# Adafruit_Feather_M0_Adalogger.net
KiCad netlist of a schematic drawn in EAGLE
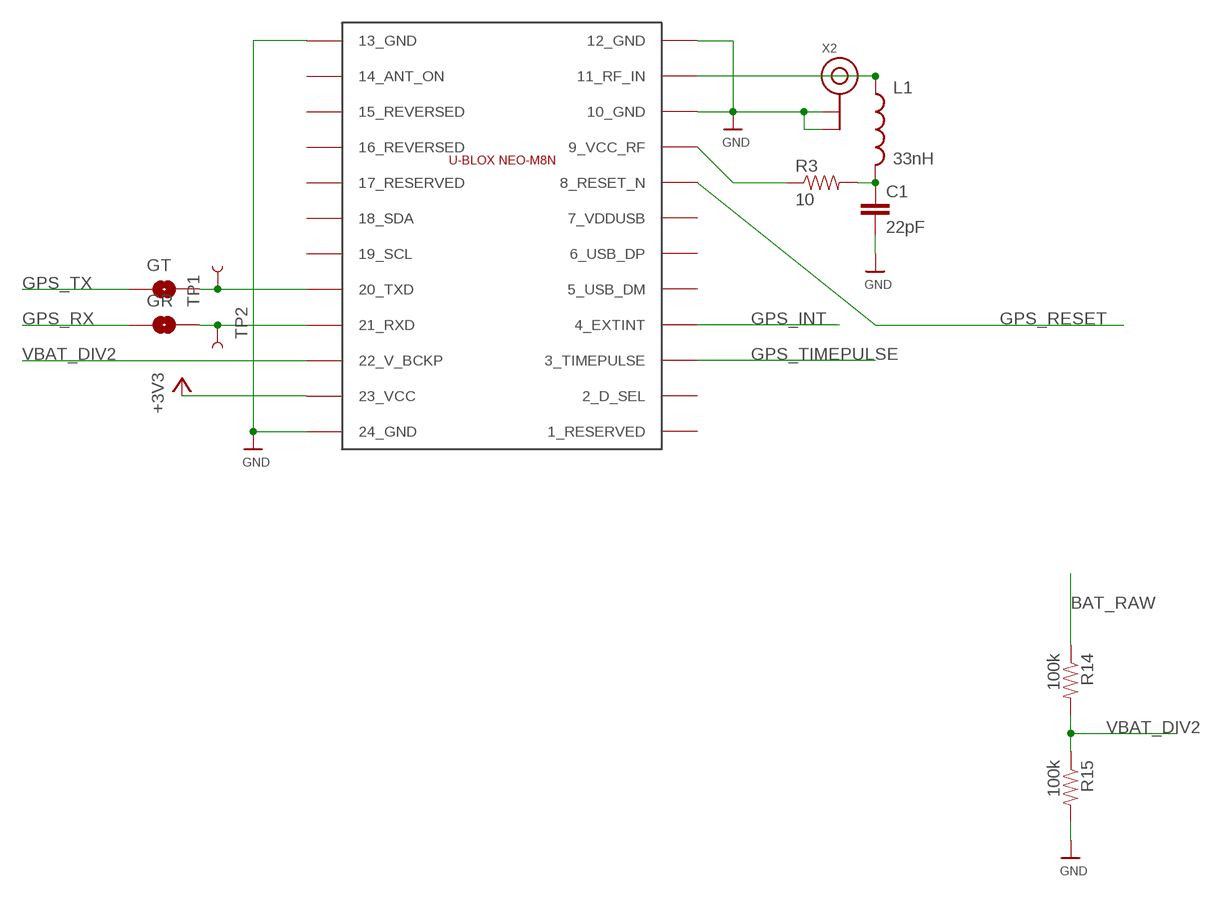
[diagram p0: schematic, sheet 1, part 1 of 2]
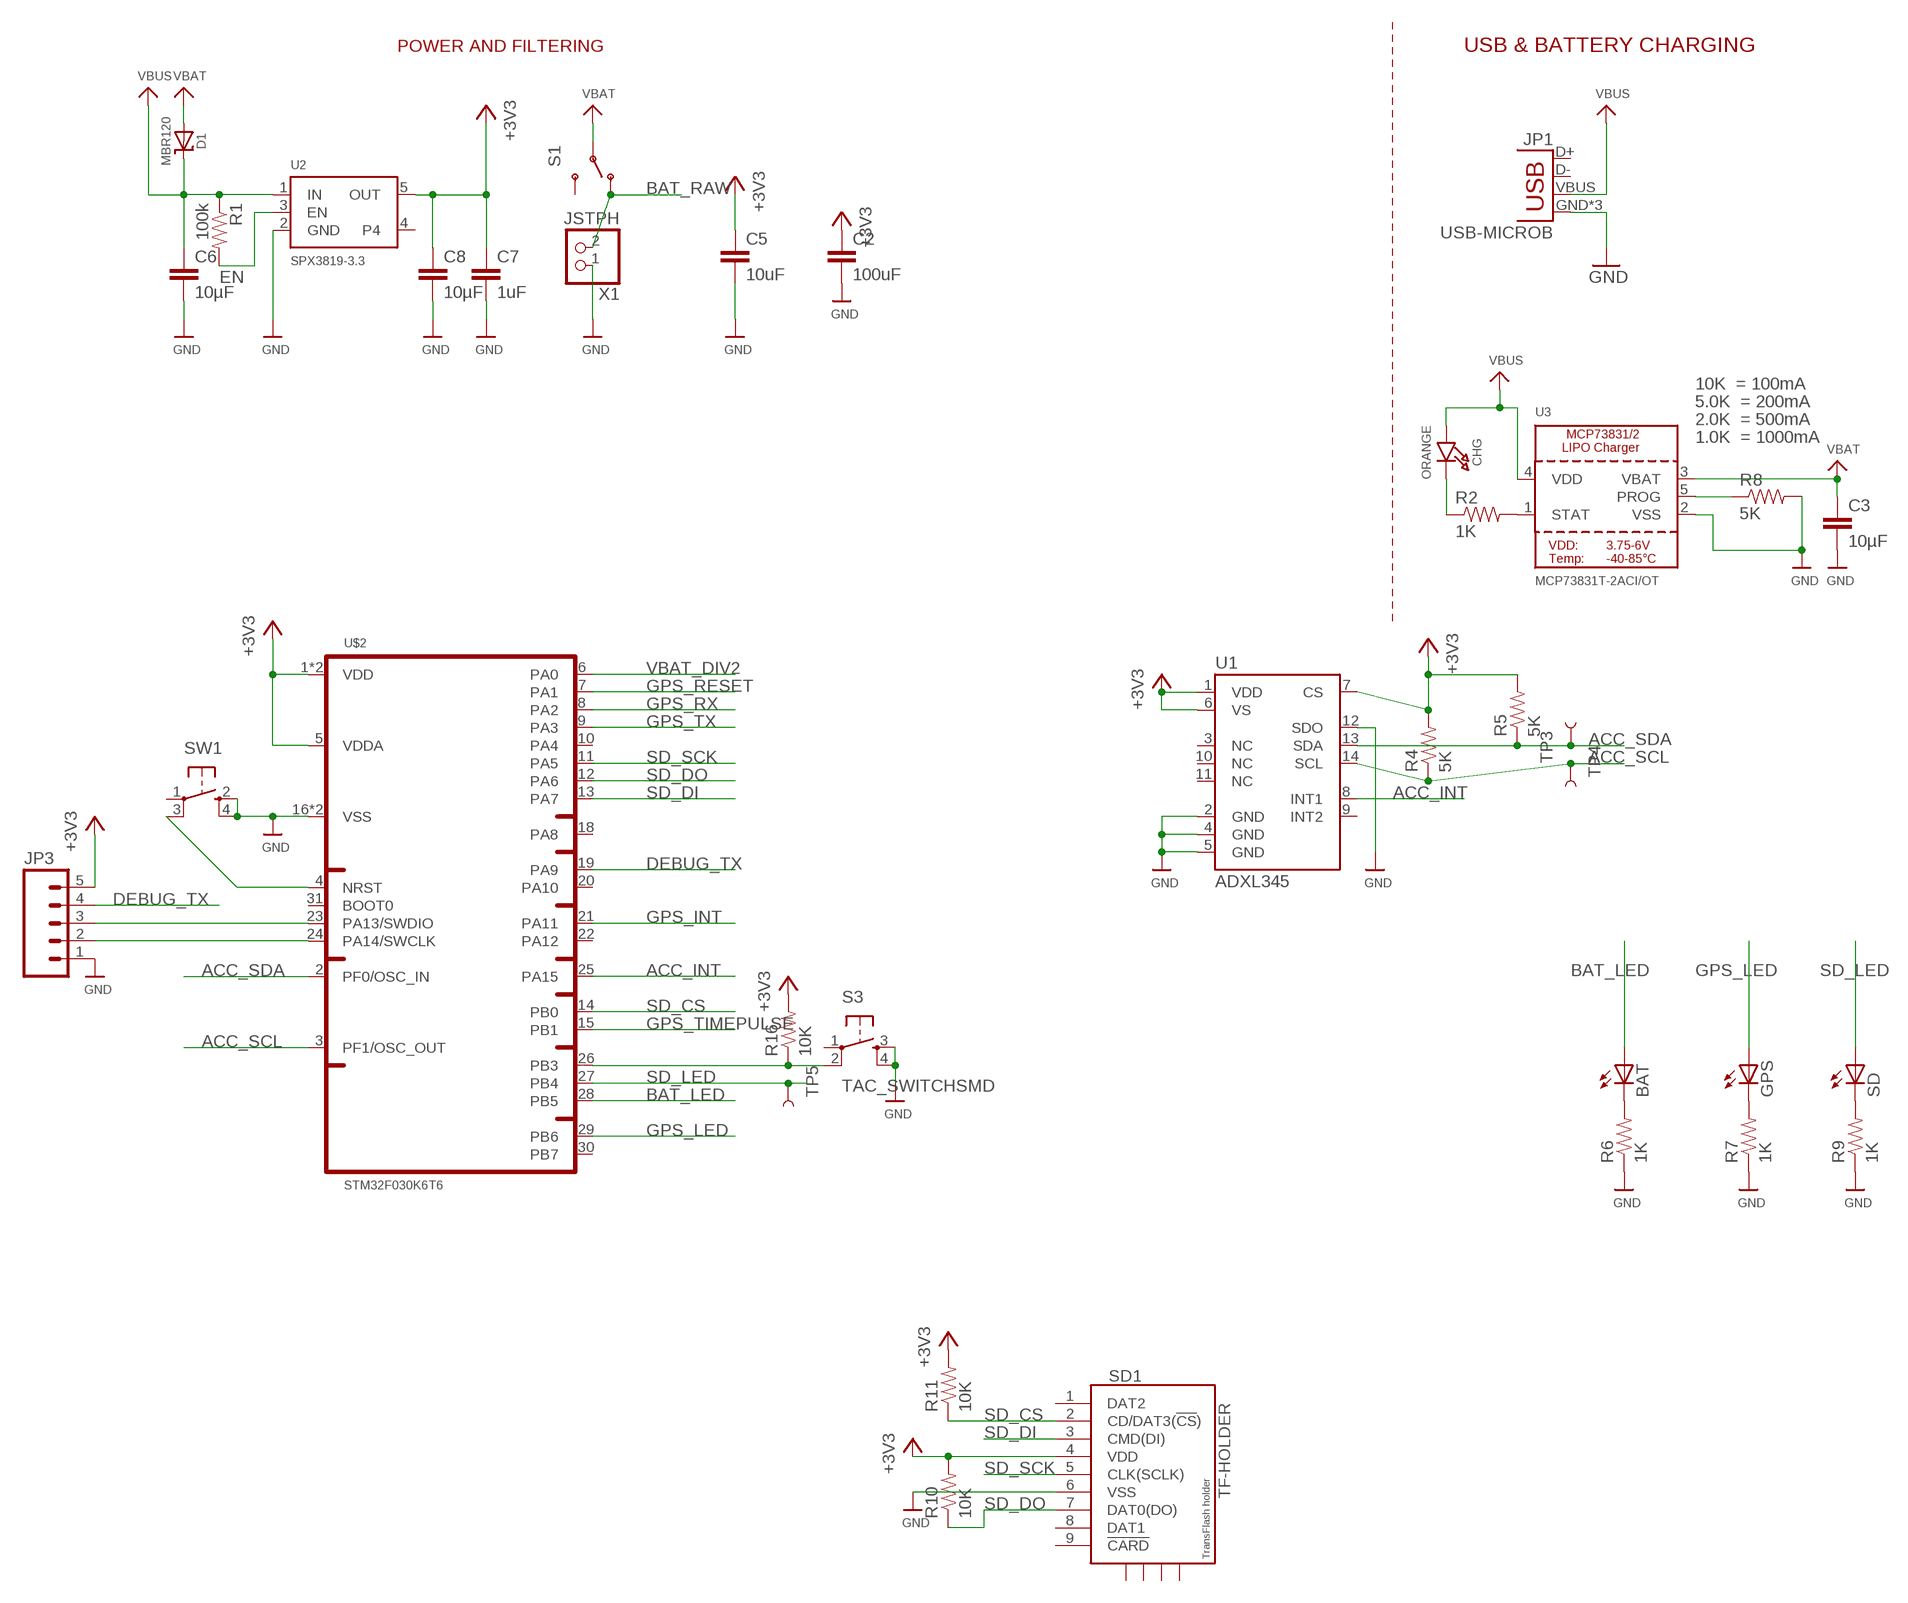
[diagram p1: schematic, sheet 1, part 2 of 2]

(export (version "E")
  (design (tool "Eeschema 10.0.6"))
  (components
    (comp (ref "BAT")
      (value "LEDCHIPLED_0805")
      (footprint "eagle-import:CHIPLED_0805")
      (libsource (lib "eagle-import") (part "LEDCHIPLED_0805"))
    )
    (comp (ref "C1")
      (value "22pF")
      (footprint "eagle-import:0805")
      (libsource (lib "eagle-import") (part "CAP0805"))
    )
    (comp (ref "C2")
      (value "100uF")
      (footprint "eagle-import:1210")
      (libsource (lib "eagle-import") (part "100UF6.3V20%(1210)"))
    )
    (comp (ref "C3")
      (value "10µF")
      (footprint "eagle-import:0805")
      (libsource (lib "eagle-import") (part "CAP0805"))
    )
    (comp (ref "C5")
      (value "10uF")
      (footprint "eagle-import:0805")
      (libsource (lib "eagle-import") (part "CAP0805"))
    )
    (comp (ref "C6")
      (value "10µF")
      (footprint "eagle-import:0805")
      (libsource (lib "eagle-import") (part "CAP0805"))
    )
    (comp (ref "C7")
      (value "1uF")
      (footprint "eagle-import:0805")
      (libsource (lib "eagle-import") (part "CAP0805"))
    )
    (comp (ref "C8")
      (value "10µF")
      (footprint "eagle-import:0805")
      (libsource (lib "eagle-import") (part "CAP0805"))
    )
    (comp (ref "CHG")
      (value "ORANGE")
      (footprint "eagle-import:CHIPLED_0805_NOOUTLINE")
      (libsource (lib "eagle-import") (part "LED0805_NOOUTLINE"))
    )
    (comp (ref "D1")
      (value "MBR120")
      (footprint "eagle-import:SOD-123")
      (libsource (lib "eagle-import") (part "DIODE-SCHOTTKYSOD-123"))
    )
    (comp (ref "DEKU1")
      (value "UBLOX_NEO-M8N")
      (footprint "eagle-import:UBLOX_NEO-M8N")
      (libsource (lib "eagle-import") (part "UBLOX_NEO-M8N"))
    )
    (comp (ref "GPS")
      (value "LEDCHIPLED_0805")
      (footprint "eagle-import:CHIPLED_0805")
      (libsource (lib "eagle-import") (part "LEDCHIPLED_0805"))
    )
    (comp (ref "GR")
      (value "JUMPER-PAD-2-NO")
      (footprint "eagle-import:PAD-JUMPER-2-NO_NO_SILK")
      (libsource (lib "eagle-import") (part "JUMPER-PAD-2-NO"))
    )
    (comp (ref "GT")
      (value "JUMPER-PAD-2-NO")
      (footprint "eagle-import:PAD-JUMPER-2-NO_NO_SILK")
      (libsource (lib "eagle-import") (part "JUMPER-PAD-2-NO"))
    )
    (comp (ref "JP1")
      (value "USB-MICROB")
      (footprint "eagle-import:USB-MICROB")
      (libsource (lib "eagle-import") (part "USB-MICROB"))
    )
    (comp (ref "JP3")
      (value "M05NO_SILK")
      (footprint "eagle-import:1X05_NO_SILK")
      (libsource (lib "eagle-import") (part "M05NO_SILK"))
    )
    (comp (ref "L1")
      (value "33nH")
      (footprint "eagle-import:0805")
      (libsource (lib "eagle-import") (part "INDUCTOR0805"))
    )
    (comp (ref "R1")
      (value "100k")
      (footprint "eagle-import:0805")
      (libsource (lib "eagle-import") (part "RESISTOR0805-RES"))
    )
    (comp (ref "R2")
      (value "1K")
      (footprint "eagle-import:0805")
      (libsource (lib "eagle-import") (part "RESISTOR0805-RES"))
    )
    (comp (ref "R3")
      (value "10")
      (footprint "eagle-import:0805")
      (libsource (lib "eagle-import") (part "RESISTOR0805-RES"))
    )
    (comp (ref "R4")
      (value "5K")
      (footprint "eagle-import:0805")
      (libsource (lib "eagle-import") (part "RESISTOR0805-RES"))
    )
    (comp (ref "R5")
      (value "5K")
      (footprint "eagle-import:0805")
      (libsource (lib "eagle-import") (part "RESISTOR0805-RES"))
    )
    (comp (ref "R6")
      (value "1K")
      (footprint "eagle-import:0805")
      (libsource (lib "eagle-import") (part "RESISTOR0805-RES"))
    )
    (comp (ref "R7")
      (value "1K")
      (footprint "eagle-import:0805")
      (libsource (lib "eagle-import") (part "RESISTOR0805-RES"))
    )
    (comp (ref "R8")
      (value "5K")
      (footprint "eagle-import:0805")
      (libsource (lib "eagle-import") (part "RESISTOR0805-RES"))
    )
    (comp (ref "R9")
      (value "1K")
      (footprint "eagle-import:0805")
      (libsource (lib "eagle-import") (part "RESISTOR0805-RES"))
    )
    (comp (ref "R10")
      (value "10K")
      (footprint "eagle-import:0805")
      (libsource (lib "eagle-import") (part "RESISTOR0805-RES"))
    )
    (comp (ref "R11")
      (value "10K")
      (footprint "eagle-import:0805")
      (libsource (lib "eagle-import") (part "RESISTOR0805-RES"))
    )
    (comp (ref "R14")
      (value "100k")
      (footprint "eagle-import:0805")
      (libsource (lib "eagle-import") (part "RESISTOR0805-RES"))
    )
    (comp (ref "R15")
      (value "100k")
      (footprint "eagle-import:0805")
      (libsource (lib "eagle-import") (part "RESISTOR0805-RES"))
    )
    (comp (ref "R16")
      (value "10K")
      (footprint "eagle-import:0805")
      (libsource (lib "eagle-import") (part "RESISTOR0805-RES"))
    )
    (comp (ref "S1")
      (value "SWITCH-SPDT-SMD-A")
      (footprint "eagle-import:SWITCH-SPST-SMD-A")
      (libsource (lib "eagle-import") (part "SWITCH-SPDT-SMD-A"))
    )
    (comp (ref "S3")
      (value "TAC_SWITCHSMD")
      (footprint "eagle-import:TACTILE-SWITCH-SMD")
      (libsource (lib "eagle-import") (part "TAC_SWITCHSMD"))
    )
    (comp (ref "SD")
      (value "LEDCHIPLED_0805")
      (footprint "eagle-import:CHIPLED_0805")
      (libsource (lib "eagle-import") (part "LEDCHIPLED_0805"))
    )
    (comp (ref "SD1")
      (value "TF-HOLDER")
      (footprint "eagle-import:TF-PULL")
      (libsource (lib "eagle-import") (part "TF-HOLDER"))
    )
    (comp (ref "SW1")
      (value "SPST_TACT-KMR2")
      (footprint "eagle-import:KMR2")
      (libsource (lib "eagle-import") (part "SPST_TACT-KMR2"))
    )
    (comp (ref "TP1")
      (value "TEST-POINT3X5")
      (footprint "eagle-import:PAD.03X.05")
      (libsource (lib "eagle-import") (part "TEST-POINT3X5"))
    )
    (comp (ref "TP2")
      (value "TEST-POINT3X5")
      (footprint "eagle-import:PAD.03X.05")
      (libsource (lib "eagle-import") (part "TEST-POINT3X5"))
    )
    (comp (ref "TP3")
      (value "TEST-POINT3")
      (footprint "eagle-import:PAD.03X.03")
      (libsource (lib "eagle-import") (part "TEST-POINT3"))
    )
    (comp (ref "TP4")
      (value "TEST-POINT3X5")
      (footprint "eagle-import:PAD.03X.05")
      (libsource (lib "eagle-import") (part "TEST-POINT3X5"))
    )
    (comp (ref "TP5")
      (value "TEST-POINT3X5")
      (footprint "eagle-import:PAD.03X.05")
      (libsource (lib "eagle-import") (part "TEST-POINT3X5"))
    )
    (comp (ref "U$2")
      (value "STM32F030K6T6")
      (footprint "eagle-import:TQFP32-08")
      (libsource (lib "eagle-import") (part "STM32F030K6T6"))
    )
    (comp (ref "U1")
      (value "ADXL345")
      (footprint "eagle-import:LGA14")
      (libsource (lib "eagle-import") (part "ADXL345"))
    )
    (comp (ref "U2")
      (value "SPX3819-3.3")
      (footprint "eagle-import:SOT23-5")
      (libsource (lib "eagle-import") (part "VREG_SOT23-5"))
    )
    (comp (ref "U3")
      (value "MCP73831T-2ACI/OT")
      (footprint "eagle-import:SOT23-5")
      (libsource (lib "eagle-import") (part "MCP73831/2"))
    )
    (comp (ref "X1")
      (value "JSTPH")
      (footprint "eagle-import:JSTPH2")
      (libsource (lib "eagle-import") (part "CON_JST_PH_2PIN"))
    )
    (comp (ref "X2")
      (value "ANTENNA_U.FL")
      (footprint "eagle-import:U.FL")
      (libsource (lib "eagle-import") (part "ANTENNA_U.FL"))
    )
  )
  (nets
    (net (code "1") (name "+3V3") (class "Default")
      (node (ref "C2") (pin "1") (pinfunction "1_1") (pintype "passive"))
      (node (ref "C5") (pin "1") (pinfunction "1_1") (pintype "passive"))
      (node (ref "C7") (pin "1") (pinfunction "1_1") (pintype "passive"))
      (node (ref "C8") (pin "1") (pinfunction "1_1") (pintype "passive"))
      (node (ref "DEKU1") (pin "23_VCC") (pinfunction "23_VCC_23_VCC") (pintype "bidirectional"))
      (node (ref "JP3") (pin "5") (pinfunction "5_5") (pintype "passive"))
      (node (ref "R10") (pin "2") (pinfunction "2_2") (pintype "passive"))
      (node (ref "R11") (pin "2") (pinfunction "2_2") (pintype "passive"))
      (node (ref "R16") (pin "2") (pinfunction "2_2") (pintype "passive"))
      (node (ref "R4") (pin "2") (pinfunction "2_2") (pintype "passive"))
      (node (ref "R5") (pin "2") (pinfunction "2_2") (pintype "passive"))
      (node (ref "SD1") (pin "4") (pinfunction "VDD_4") (pintype "power_in"))
      (node (ref "U$2") (pin "1") (pinfunction "VDD_1") (pintype "bidirectional"))
      (node (ref "U$2") (pin "17") (pinfunction "VDD_17") (pintype "bidirectional"))
      (node (ref "U$2") (pin "5") (pinfunction "VDDA_5") (pintype "bidirectional"))
      (node (ref "U1") (pin "1") (pinfunction "VDD_1") (pintype "bidirectional"))
      (node (ref "U1") (pin "6") (pinfunction "VS_6") (pintype "bidirectional"))
      (node (ref "U1") (pin "7") (pinfunction "CS_7") (pintype "bidirectional"))
      (node (ref "U2") (pin "5") (pinfunction "OUT_5") (pintype "power_in"))
    )
    (net (code "2") (name "/ACC_INT") (class "Default")
      (node (ref "U$2") (pin "25") (pinfunction "PA15_25") (pintype "bidirectional"))
      (node (ref "U1") (pin "8") (pinfunction "INT1_8") (pintype "bidirectional"))
    )
    (net (code "3") (name "/ACC_SCL") (class "Default")
      (node (ref "R4") (pin "1") (pinfunction "1_1") (pintype "passive"))
      (node (ref "TP4") (pin "P$1") (pinfunction "1_P$1") (pintype "bidirectional"))
      (node (ref "U$2") (pin "3") (pinfunction "PF1/OSC_OUT_3") (pintype "bidirectional"))
      (node (ref "U1") (pin "14") (pinfunction "SCL_14") (pintype "bidirectional"))
    )
    (net (code "4") (name "/ACC_SDA") (class "Default")
      (node (ref "R5") (pin "1") (pinfunction "1_1") (pintype "passive"))
      (node (ref "TP3") (pin "P$1") (pinfunction "1_P$1") (pintype "bidirectional"))
      (node (ref "U$2") (pin "2") (pinfunction "PF0/OSC_IN_2") (pintype "bidirectional"))
      (node (ref "U1") (pin "13") (pinfunction "SDA_13") (pintype "bidirectional"))
    )
    (net (code "5") (name "/BAT_LED") (class "Default")
      (node (ref "BAT") (pin "A") (pinfunction "A_A") (pintype "passive"))
      (node (ref "U$2") (pin "28") (pinfunction "PB5_28") (pintype "bidirectional"))
    )
    (net (code "6") (name "/BAT_RAW") (class "Default")
      (node (ref "R14") (pin "1") (pinfunction "1_1") (pintype "passive"))
      (node (ref "S1") (pin "1") (pinfunction "O_1") (pintype "passive"))
      (node (ref "X1") (pin "2") (pinfunction "2_2") (pintype "passive"))
    )
    (net (code "7") (name "/DEBUG_TX") (class "Default")
      (node (ref "JP3") (pin "4") (pinfunction "4_4") (pintype "passive"))
      (node (ref "U$2") (pin "19") (pinfunction "PA9_19") (pintype "bidirectional"))
    )
    (net (code "8") (name "/EN") (class "Default")
      (node (ref "R1") (pin "2") (pinfunction "2_2") (pintype "passive"))
      (node (ref "U2") (pin "3") (pinfunction "EN_3") (pintype "input"))
    )
    (net (code "9") (name "/GPS_INT") (class "Default")
      (node (ref "DEKU1") (pin "4_EXTINT") (pinfunction "4_EXTINT_4_EXTINT") (pintype "bidirectional"))
      (node (ref "U$2") (pin "21") (pinfunction "PA11_21") (pintype "bidirectional"))
    )
    (net (code "10") (name "/GPS_LED") (class "Default")
      (node (ref "GPS") (pin "A") (pinfunction "A_A") (pintype "passive"))
      (node (ref "U$2") (pin "29") (pinfunction "PB6_29") (pintype "bidirectional"))
    )
    (net (code "11") (name "/GPS_RESET") (class "Default")
      (node (ref "DEKU1") (pin "8_RESET_N") (pinfunction "8_RESET_N_8_RESET_N") (pintype "bidirectional"))
      (node (ref "U$2") (pin "7") (pinfunction "PA1_7") (pintype "bidirectional"))
    )
    (net (code "12") (name "/GPS_RX") (class "Default")
      (node (ref "GR") (pin "1") (pinfunction "1_1") (pintype "passive"))
      (node (ref "U$2") (pin "8") (pinfunction "PA2_8") (pintype "bidirectional"))
    )
    (net (code "13") (name "/GPS_TIMEPULSE") (class "Default")
      (node (ref "DEKU1") (pin "3_TIMEPULSE") (pinfunction "3_TIMEPULSE_3_TIMEPULSE") (pintype "bidirectional"))
      (node (ref "U$2") (pin "15") (pinfunction "PB1_15") (pintype "bidirectional"))
    )
    (net (code "14") (name "/GPS_TX") (class "Default")
      (node (ref "GT") (pin "1") (pinfunction "1_1") (pintype "passive"))
      (node (ref "U$2") (pin "9") (pinfunction "PA3_9") (pintype "bidirectional"))
    )
    (net (code "15") (name "/SD_CS") (class "Default")
      (node (ref "R11") (pin "1") (pinfunction "1_1") (pintype "passive"))
      (node (ref "SD1") (pin "2") (pinfunction "CD/DAT3(~{CS})_2") (pintype "bidirectional"))
      (node (ref "U$2") (pin "14") (pinfunction "PB0_14") (pintype "bidirectional"))
    )
    (net (code "16") (name "/SD_DI") (class "Default")
      (node (ref "SD1") (pin "3") (pinfunction "CMD(DI)_3") (pintype "bidirectional"))
      (node (ref "U$2") (pin "13") (pinfunction "PA7_13") (pintype "bidirectional"))
    )
    (net (code "17") (name "/SD_DO") (class "Default")
      (node (ref "R10") (pin "1") (pinfunction "1_1") (pintype "passive"))
      (node (ref "SD1") (pin "7") (pinfunction "DAT0(DO)_7") (pintype "bidirectional"))
      (node (ref "U$2") (pin "12") (pinfunction "PA6_12") (pintype "bidirectional"))
    )
    (net (code "18") (name "/SD_LED") (class "Default")
      (node (ref "SD") (pin "A") (pinfunction "A_A") (pintype "passive"))
      (node (ref "TP5") (pin "P$1") (pinfunction "1_P$1") (pintype "bidirectional"))
      (node (ref "U$2") (pin "27") (pinfunction "PB4_27") (pintype "bidirectional"))
    )
    (net (code "19") (name "/SD_SCK") (class "Default")
      (node (ref "SD1") (pin "5") (pinfunction "CLK(SCLK)_5") (pintype "input"))
      (node (ref "U$2") (pin "11") (pinfunction "PA5_11") (pintype "bidirectional"))
    )
    (net (code "20") (name "/VBAT_DIV2") (class "Default")
      (node (ref "DEKU1") (pin "22_V_BCKP") (pinfunction "22_V_BCKP_22_V_BCKP") (pintype "bidirectional"))
      (node (ref "R14") (pin "2") (pinfunction "2_2") (pintype "passive"))
      (node (ref "R15") (pin "1") (pinfunction "1_1") (pintype "passive"))
      (node (ref "U$2") (pin "6") (pinfunction "PA0_6") (pintype "bidirectional"))
    )
    (net (code "21") (name "GND") (class "Default")
      (node (ref "C1") (pin "2") (pinfunction "2_2") (pintype "passive"))
      (node (ref "C2") (pin "2") (pinfunction "2_2") (pintype "passive"))
      (node (ref "C3") (pin "2") (pinfunction "2_2") (pintype "passive"))
      (node (ref "C5") (pin "2") (pinfunction "2_2") (pintype "passive"))
      (node (ref "C6") (pin "2") (pinfunction "2_2") (pintype "passive"))
      (node (ref "C7") (pin "2") (pinfunction "2_2") (pintype "passive"))
      (node (ref "C8") (pin "2") (pinfunction "2_2") (pintype "passive"))
      (node (ref "DEKU1") (pin "10_GND") (pinfunction "10_GND_10_GND") (pintype "bidirectional"))
      (node (ref "DEKU1") (pin "12_GND") (pinfunction "12_GND_12_GND") (pintype "bidirectional"))
      (node (ref "DEKU1") (pin "13_GND") (pinfunction "13_GND_13_GND") (pintype "bidirectional"))
      (node (ref "DEKU1") (pin "24_GND") (pinfunction "24_GND_24_GND") (pintype "bidirectional"))
      (node (ref "JP1") (pin "GND") (pinfunction "GND_GND") (pintype "bidirectional"))
      (node (ref "JP1") (pin "MT1") (pinfunction "GND_MT1") (pintype "bidirectional"))
      (node (ref "JP1") (pin "MT2") (pinfunction "GND_MT2") (pintype "bidirectional"))
      (node (ref "JP3") (pin "1") (pinfunction "1_1") (pintype "passive"))
      (node (ref "R15") (pin "2") (pinfunction "2_2") (pintype "passive"))
      (node (ref "R6") (pin "1") (pinfunction "1_1") (pintype "passive"))
      (node (ref "R7") (pin "1") (pinfunction "1_1") (pintype "passive"))
      (node (ref "R8") (pin "2") (pinfunction "2_2") (pintype "passive"))
      (node (ref "R9") (pin "1") (pinfunction "1_1") (pintype "passive"))
      (node (ref "S3") (pin "3") (pinfunction "3_3") (pintype "passive"))
      (node (ref "S3") (pin "4") (pinfunction "4_4") (pintype "passive"))
      (node (ref "SD1") (pin "6") (pinfunction "VSS_6") (pintype "power_in"))
      (node (ref "SW1") (pin "2") (pinfunction "S_2") (pintype "passive"))
      (node (ref "SW1") (pin "4") (pinfunction "S1_4") (pintype "passive"))
      (node (ref "U$2") (pin "16") (pinfunction "VSS_16") (pintype "bidirectional"))
      (node (ref "U$2") (pin "32") (pinfunction "VSS_32") (pintype "bidirectional"))
      (node (ref "U1") (pin "12") (pinfunction "SDO_12") (pintype "bidirectional"))
      (node (ref "U1") (pin "2") (pinfunction "GND_2") (pintype "bidirectional"))
      (node (ref "U1") (pin "4") (pinfunction "GND_4") (pintype "bidirectional"))
      (node (ref "U1") (pin "5") (pinfunction "GND_5") (pintype "bidirectional"))
      (node (ref "U2") (pin "2") (pinfunction "GND_2") (pintype "power_in"))
      (node (ref "U3") (pin "2") (pinfunction "VSS_2") (pintype "power_in"))
      (node (ref "X1") (pin "1") (pinfunction "1_1") (pintype "passive"))
      (node (ref "X2") (pin "1") (pinfunction "GND_1") (pintype "passive"))
      (node (ref "X2") (pin "2") (pinfunction "GND_2") (pintype "passive"))
    )
    (net (code "22") (name "Net-(BAT-PadC)") (class "Default")
      (node (ref "BAT") (pin "C") (pinfunction "C_C") (pintype "passive"))
      (node (ref "R6") (pin "2") (pinfunction "2_2") (pintype "passive"))
    )
    (net (code "23") (name "Net-(C1-Pad1)") (class "Default")
      (node (ref "C1") (pin "1") (pinfunction "1_1") (pintype "passive"))
      (node (ref "L1") (pin "2") (pinfunction "2_2") (pintype "passive"))
      (node (ref "R3") (pin "2") (pinfunction "2_2") (pintype "passive"))
    )
    (net (code "24") (name "Net-(CHG-PadC)") (class "Default")
      (node (ref "CHG") (pin "C") (pinfunction "C_C") (pintype "passive"))
      (node (ref "R2") (pin "1") (pinfunction "1_1") (pintype "passive"))
    )
    (net (code "25") (name "Net-(DEKU1-Pad9_VCC_RF)") (class "Default")
      (node (ref "DEKU1") (pin "9_VCC_RF") (pinfunction "9_VCC_RF_9_VCC_RF") (pintype "bidirectional"))
      (node (ref "R3") (pin "1") (pinfunction "1_1") (pintype "passive"))
    )
    (net (code "26") (name "Net-(GPS-PadC)") (class "Default")
      (node (ref "GPS") (pin "C") (pinfunction "C_C") (pintype "passive"))
      (node (ref "R7") (pin "2") (pinfunction "2_2") (pintype "passive"))
    )
    (net (code "27") (name "Net-(R9-Pad2)") (class "Default")
      (node (ref "R9") (pin "2") (pinfunction "2_2") (pintype "passive"))
      (node (ref "SD") (pin "C") (pinfunction "C_C") (pintype "passive"))
    )
    (net (code "28") (name "Net-(SW1-P1)") (class "Default")
      (node (ref "SW1") (pin "3") (pinfunction "P1_3") (pintype "passive"))
      (node (ref "U$2") (pin "4") (pinfunction "NRST_4") (pintype "bidirectional"))
    )
    (net (code "29") (name "Net-(TP1-1)") (class "Default")
      (node (ref "DEKU1") (pin "20_TXD") (pinfunction "20_TXD_20_TXD") (pintype "bidirectional"))
      (node (ref "GT") (pin "2") (pinfunction "2_2") (pintype "passive"))
      (node (ref "TP1") (pin "P$1") (pinfunction "1_P$1") (pintype "bidirectional"))
    )
    (net (code "30") (name "Net-(TP2-1)") (class "Default")
      (node (ref "DEKU1") (pin "21_RXD") (pinfunction "21_RXD_21_RXD") (pintype "bidirectional"))
      (node (ref "GR") (pin "2") (pinfunction "2_2") (pintype "passive"))
      (node (ref "TP2") (pin "P$1") (pinfunction "1_P$1") (pintype "bidirectional"))
    )
    (net (code "31") (name "Net-(U$2-PA13{slash}SWDIO)") (class "Default")
      (node (ref "JP3") (pin "3") (pinfunction "3_3") (pintype "passive"))
      (node (ref "U$2") (pin "23") (pinfunction "PA13/SWDIO_23") (pintype "bidirectional"))
    )
    (net (code "32") (name "Net-(U$2-PA14{slash}SWCLK)") (class "Default")
      (node (ref "JP3") (pin "2") (pinfunction "2_2") (pintype "passive"))
      (node (ref "U$2") (pin "24") (pinfunction "PA14/SWCLK_24") (pintype "bidirectional"))
    )
    (net (code "33") (name "Net-(U$2-PB3)") (class "Default")
      (node (ref "R16") (pin "1") (pinfunction "1_1") (pintype "passive"))
      (node (ref "S3") (pin "2") (pinfunction "2_2") (pintype "passive"))
      (node (ref "U$2") (pin "26") (pinfunction "PB3_26") (pintype "bidirectional"))
    )
    (net (code "34") (name "Net-(U3-PROG)") (class "Default")
      (node (ref "R8") (pin "1") (pinfunction "1_1") (pintype "passive"))
      (node (ref "U3") (pin "5") (pinfunction "PROG_5") (pintype "input"))
    )
    (net (code "35") (name "Net-(U3-STAT)") (class "Default")
      (node (ref "R2") (pin "2") (pinfunction "2_2") (pintype "passive"))
      (node (ref "U3") (pin "1") (pinfunction "STAT_1") (pintype "output"))
    )
    (net (code "36") (name "Net-(X2-SIGNAL)") (class "Default")
      (node (ref "DEKU1") (pin "11_RF_IN") (pinfunction "11_RF_IN_11_RF_IN") (pintype "bidirectional"))
      (node (ref "L1") (pin "1") (pinfunction "1_1") (pintype "passive"))
      (node (ref "X2") (pin "3") (pinfunction "SIGNAL_3") (pintype "passive"))
    )
    (net (code "37") (name "VBAT") (class "Default")
      (node (ref "C3") (pin "1") (pinfunction "1_1") (pintype "passive"))
      (node (ref "D1") (pin "A") (pinfunction "A_A") (pintype "passive"))
      (node (ref "S1") (pin "2") (pinfunction "P_2") (pintype "passive"))
      (node (ref "U3") (pin "3") (pinfunction "VBAT_3") (pintype "power_in"))
    )
    (net (code "38") (name "VBUS") (class "Default")
      (node (ref "C6") (pin "1") (pinfunction "1_1") (pintype "passive"))
      (node (ref "CHG") (pin "A") (pinfunction "A_A") (pintype "passive"))
      (node (ref "D1") (pin "C") (pinfunction "C_C") (pintype "passive"))
      (node (ref "JP1") (pin "VBUS") (pinfunction "VBUS_VBUS") (pintype "bidirectional"))
      (node (ref "R1") (pin "1") (pinfunction "1_1") (pintype "passive"))
      (node (ref "U2") (pin "1") (pinfunction "IN_1") (pintype "power_in"))
      (node (ref "U3") (pin "4") (pinfunction "VDD_4") (pintype "power_in"))
    )
    (net (code "39") (name "unconnected-(DEKU1-Pad1_RESERVED)") (class "Default")
      (node (ref "DEKU1") (pin "1_RESERVED") (pinfunction "1_RESERVED_1_RESERVED") (pintype "bidirectional"))
    )
    (net (code "40") (name "unconnected-(DEKU1-Pad2_D_SEL)") (class "Default")
      (node (ref "DEKU1") (pin "2_D_SEL") (pinfunction "2_D_SEL_2_D_SEL") (pintype "bidirectional"))
    )
    (net (code "41") (name "unconnected-(DEKU1-Pad5_USB_DM)") (class "Default")
      (node (ref "DEKU1") (pin "5_USB_DM") (pinfunction "5_USB_DM_5_USB_DM") (pintype "bidirectional"))
    )
    (net (code "42") (name "unconnected-(DEKU1-Pad6_USB_DP)") (class "Default")
      (node (ref "DEKU1") (pin "6_USB_DP") (pinfunction "6_USB_DP_6_USB_DP") (pintype "bidirectional"))
    )
    (net (code "43") (name "unconnected-(DEKU1-Pad7_VDDUSB)") (class "Default")
      (node (ref "DEKU1") (pin "7_VDDUSB") (pinfunction "7_VDDUSB_7_VDDUSB") (pintype "bidirectional"))
    )
    (net (code "44") (name "unconnected-(DEKU1-Pad14_ANT_ON)") (class "Default")
      (node (ref "DEKU1") (pin "14_ANT_ON") (pinfunction "14_ANT_ON_14_ANT_ON") (pintype "bidirectional"))
    )
    (net (code "45") (name "unconnected-(DEKU1-Pad15_REVERSED)") (class "Default")
      (node (ref "DEKU1") (pin "15_REVERSED") (pinfunction "15_REVERSED_15_REVERSED") (pintype "bidirectional"))
    )
    (net (code "46") (name "unconnected-(DEKU1-Pad16_REVERSED)") (class "Default")
      (node (ref "DEKU1") (pin "16_REVERSED") (pinfunction "16_REVERSED_16_REVERSED") (pintype "bidirectional"))
    )
    (net (code "47") (name "unconnected-(DEKU1-Pad17_RESERVED)") (class "Default")
      (node (ref "DEKU1") (pin "17_RESERVED") (pinfunction "17_RESERVED_17_RESERVED") (pintype "bidirectional"))
    )
    (net (code "48") (name "unconnected-(DEKU1-Pad18_SDA)") (class "Default")
      (node (ref "DEKU1") (pin "18_SDA") (pinfunction "18_SDA_18_SDA") (pintype "bidirectional"))
    )
    (net (code "49") (name "unconnected-(DEKU1-Pad19_SCL)") (class "Default")
      (node (ref "DEKU1") (pin "19_SCL") (pinfunction "19_SCL_19_SCL") (pintype "bidirectional"))
    )
    (net (code "50") (name "unconnected-(JP1-PadD+)") (class "Default")
      (node (ref "JP1") (pin "D+") (pinfunction "D+_D+") (pintype "bidirectional"))
    )
    (net (code "51") (name "unconnected-(JP1-PadD-)") (class "Default")
      (node (ref "JP1") (pin "D-") (pinfunction "D-_D-") (pintype "bidirectional"))
    )
    (net (code "52") (name "unconnected-(S1-S-Pad3)") (class "Default")
      (node (ref "S1") (pin "3") (pinfunction "S_3") (pintype "passive"))
    )
    (net (code "53") (name "unconnected-(S3-Pad1)") (class "Default")
      (node (ref "S3") (pin "1") (pinfunction "1_1") (pintype "passive"))
    )
    (net (code "54") (name "unconnected-(SD1-DAT1-Pad8)") (class "Default")
      (node (ref "SD1") (pin "8") (pinfunction "DAT1_8") (pintype "bidirectional"))
    )
    (net (code "55") (name "unconnected-(SD1-DAT2-Pad1)") (class "Default")
      (node (ref "SD1") (pin "1") (pinfunction "DAT2_1") (pintype "bidirectional"))
    )
    (net (code "56") (name "unconnected-(SD1-PadS1)") (class "Default")
      (node (ref "SD1") (pin "S1") (pinfunction "S1_S1") (pintype "passive"))
    )
    (net (code "57") (name "unconnected-(SD1-PadS2)") (class "Default")
      (node (ref "SD1") (pin "S2") (pinfunction "S2_S2") (pintype "passive"))
    )
    (net (code "58") (name "unconnected-(SD1-PadS3)") (class "Default")
      (node (ref "SD1") (pin "S3") (pinfunction "S3_S3") (pintype "passive"))
    )
    (net (code "59") (name "unconnected-(SD1-PadS4)") (class "Default")
      (node (ref "SD1") (pin "S4") (pinfunction "S4_S4") (pintype "passive"))
    )
    (net (code "60") (name "unconnected-(SD1-~{CARD}-Pad9)") (class "Default")
      (node (ref "SD1") (pin "9") (pinfunction "~{CARD}_9") (pintype "passive"))
    )
    (net (code "61") (name "unconnected-(SW1-P-Pad1)") (class "Default")
      (node (ref "SW1") (pin "1") (pinfunction "P_1") (pintype "passive"))
    )
    (net (code "62") (name "unconnected-(U$2-BOOT0-Pad31)") (class "Default")
      (node (ref "U$2") (pin "31") (pinfunction "BOOT0_31") (pintype "bidirectional"))
    )
    (net (code "63") (name "unconnected-(U$2-PA4-Pad10)") (class "Default")
      (node (ref "U$2") (pin "10") (pinfunction "PA4_10") (pintype "bidirectional"))
    )
    (net (code "64") (name "unconnected-(U$2-PA8-Pad18)") (class "Default")
      (node (ref "U$2") (pin "18") (pinfunction "PA8_18") (pintype "bidirectional"))
    )
    (net (code "65") (name "unconnected-(U$2-PA10-Pad20)") (class "Default")
      (node (ref "U$2") (pin "20") (pinfunction "PA10_20") (pintype "bidirectional"))
    )
    (net (code "66") (name "unconnected-(U$2-PA12-Pad22)") (class "Default")
      (node (ref "U$2") (pin "22") (pinfunction "PA12_22") (pintype "bidirectional"))
    )
    (net (code "67") (name "unconnected-(U$2-PB7-Pad30)") (class "Default")
      (node (ref "U$2") (pin "30") (pinfunction "PB7_30") (pintype "bidirectional"))
    )
    (net (code "68") (name "unconnected-(U1-INT2-Pad9)") (class "Default")
      (node (ref "U1") (pin "9") (pinfunction "INT2_9") (pintype "bidirectional"))
    )
    (net (code "69") (name "unconnected-(U1-NC-Pad3)") (class "Default")
      (node (ref "U1") (pin "3") (pinfunction "NC_3") (pintype "bidirectional"))
    )
    (net (code "70") (name "unconnected-(U1-NC-Pad10)") (class "Default")
      (node (ref "U1") (pin "10") (pinfunction "NC_10") (pintype "bidirectional"))
    )
    (net (code "71") (name "unconnected-(U1-NC-Pad11)") (class "Default")
      (node (ref "U1") (pin "11") (pinfunction "NC_11") (pintype "bidirectional"))
    )
    (net (code "72") (name "unconnected-(U2-P4-Pad4)") (class "Default")
      (node (ref "U2") (pin "4") (pinfunction "P4_4") (pintype "bidirectional"))
    )
  )
)
